# MCU.net
KiCad netlist of a schematic drawn in Altium Designer
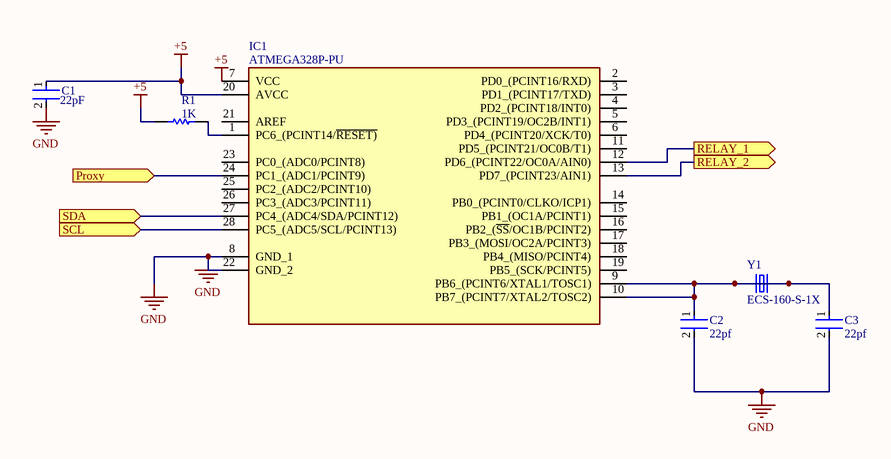
[diagram p0: MCU.SchDoc]

(export (version "E")
  (design (tool "Eeschema 10.0.6"))
  (components
    (comp (ref "C1")
      (value "22pF")
      (footprint "FP-VY2472M49Y5UG63V7-MFG")
      (description "Capacitor Ceramic 4700pF ±20% Y5U BULK RADIAL")
      (fields (field (name "TOLERANCE") "20%") (field (name "Comment") "22pf"))
      (libsource (lib "Altium Content Vault") (part "02cd4be3c70576c341d710602a673aa"))
    )
    (comp (ref "C2")
      (value "22pf")
      (footprint "FP-VY2472M49Y5UG63V7-MFG")
      (description "Capacitor Ceramic 4700pF ±20% Y5U BULK RADIAL")
      (fields (field (name "TOLERANCE") "20%"))
      (libsource (lib "Altium Content Vault") (part "02cd4be3c70576c341d710602a673aa"))
    )
    (comp (ref "C3")
      (value "22pf")
      (footprint "FP-VY2472M49Y5UG63V7-MFG")
      (description "Capacitor Ceramic 4700pF ±20% Y5U BULK RADIAL")
      (fields (field (name "TOLERANCE") "20%"))
      (libsource (lib "Altium Content Vault") (part "02cd4be3c70576c341d710602a673aa"))
    )
    (comp (ref "IC1")
      (value "ATMEGA328P-PU")
      (footprint "SamacSys:DIP794W53P254L3467H457Q28N")
      (description "Integrated Circuit")
      (fields (field (name "MOUSER PART NUMBER") "556-ATMEGA328P-PU"))
      (libsource (lib "*") (part "ATMEGA328P-PU"))
    )
    (comp (ref "R1")
      (value "1K")
      (footprint "RESA60-630X240")
      (description "Axial Resistor, 10 KOhm, +/- 1%, 0.25 W, -55 to 155 degC, 2-Pin THD, RoHS, Bulk")
      (fields (field (name "TOLERANCE") "1%") (field (name "MANUFACTURER") "Yageo"))
      (libsource (lib "Altium Content Vault") (part "RES-2"))
    )
    (comp (ref "Y1")
      (value "ECS-160-S-1X")
      (footprint "XTAL_ECS-160-S-1X")
      (description "16MHz Â±30ppm Crystal Series 20 Ohms HC-49/U")
      (fields (field (name "MF") "ECS Inc."))
      (libsource (lib "ECS-160-S-1X") (part "ECS-160-S-1X"))
    )
  )
  (nets
    (net (code "1") (name "+5") (class "Default")
      (node (ref "C1") (pin "1") (pinfunction "1_1") (pintype "passive"))
      (node (ref "IC1") (pin "20") (pinfunction "AVCC_20") (pintype "passive"))
      (node (ref "IC1") (pin "7") (pinfunction "VCC_7") (pintype "passive"))
      (node (ref "R1") (pin "1") (pinfunction "1_1") (pintype "passive"))
    )
    (net (code "2") (name "/Proxy") (class "Default")
      (node (ref "IC1") (pin "24") (pinfunction "PC1_(ADC1/PCINT9)_24") (pintype "passive"))
    )
    (net (code "3") (name "/RELAY_1") (class "Default")
      (node (ref "IC1") (pin "12") (pinfunction "PD6_(PCINT22/OC0A/AIN0)_12") (pintype "passive"))
    )
    (net (code "4") (name "/RELAY_2") (class "Default")
      (node (ref "IC1") (pin "13") (pinfunction "PD7_(PCINT23/AIN1)_13") (pintype "passive"))
    )
    (net (code "5") (name "/SCL") (class "Default")
      (node (ref "IC1") (pin "28") (pinfunction "PC5_(ADC5/SCL/PCINT13)_28") (pintype "passive"))
    )
    (net (code "6") (name "/SDA") (class "Default")
      (node (ref "IC1") (pin "27") (pinfunction "PC4_(ADC4/SDA/PCINT12)_27") (pintype "passive"))
    )
    (net (code "7") (name "GND") (class "Default")
      (node (ref "C1") (pin "2") (pinfunction "2_2") (pintype "passive"))
      (node (ref "C2") (pin "2") (pinfunction "2_2") (pintype "passive"))
      (node (ref "C3") (pin "2") (pinfunction "2_2") (pintype "passive"))
      (node (ref "IC1") (pin "22") (pinfunction "GND_2_22") (pintype "passive"))
      (node (ref "IC1") (pin "8") (pinfunction "GND_1_8") (pintype "passive"))
    )
    (net (code "8") (name "Net-(IC1-PB6_(PCINT6{slash}XTAL1{slash}TOSC1))") (class "Default")
      (node (ref "C2") (pin "1") (pinfunction "1_1") (pintype "passive"))
      (node (ref "C3") (pin "1") (pinfunction "1_1") (pintype "passive"))
      (node (ref "IC1") (pin "10") (pinfunction "PB7_(PCINT7/XTAL2/TOSC2)_10") (pintype "passive"))
      (node (ref "IC1") (pin "9") (pinfunction "PB6_(PCINT6/XTAL1/TOSC1)_9") (pintype "passive"))
      (node (ref "Y1") (pin "1") (pinfunction "1_1") (pintype "passive"))
      (node (ref "Y1") (pin "2") (pinfunction "2_2") (pintype "passive"))
    )
    (net (code "9") (name "Net-(IC1-PC6_(PCINT14{slash}~{RESET)})") (class "Default")
      (node (ref "IC1") (pin "1") (pinfunction "PC6_(PCINT14/~{RESET)}_1") (pintype "passive"))
      (node (ref "R1") (pin "2") (pinfunction "2_2") (pintype "passive"))
    )
    (net (code "10") (name "unconnected-(IC1-AREF-Pad21)") (class "Default")
      (node (ref "IC1") (pin "21") (pinfunction "AREF_21") (pintype "passive"))
    )
    (net (code "11") (name "unconnected-(IC1-PB0_(PCINT0{slash}CLKO{slash}ICP1)-Pad14)") (class "Default")
      (node (ref "IC1") (pin "14") (pinfunction "PB0_(PCINT0/CLKO/ICP1)_14") (pintype "passive"))
    )
    (net (code "12") (name "unconnected-(IC1-PB1_(OC1A{slash}PCINT1)-Pad15)") (class "Default")
      (node (ref "IC1") (pin "15") (pinfunction "PB1_(OC1A/PCINT1)_15") (pintype "passive"))
    )
    (net (code "13") (name "unconnected-(IC1-PB2_(~{SS}{slash}OC1B{slash}PCINT2)-Pad16)") (class "Default")
      (node (ref "IC1") (pin "16") (pinfunction "PB2_(~{SS}/OC1B/PCINT2)_16") (pintype "passive"))
    )
    (net (code "14") (name "unconnected-(IC1-PB3_(MOSI{slash}OC2A{slash}PCINT3)-Pad17)") (class "Default")
      (node (ref "IC1") (pin "17") (pinfunction "PB3_(MOSI/OC2A/PCINT3)_17") (pintype "passive"))
    )
    (net (code "15") (name "unconnected-(IC1-PB4_(MISO{slash}PCINT4)-Pad18)") (class "Default")
      (node (ref "IC1") (pin "18") (pinfunction "PB4_(MISO/PCINT4)_18") (pintype "passive"))
    )
    (net (code "16") (name "unconnected-(IC1-PB5_(SCK{slash}PCINT5)-Pad19)") (class "Default")
      (node (ref "IC1") (pin "19") (pinfunction "PB5_(SCK/PCINT5)_19") (pintype "passive"))
    )
    (net (code "17") (name "unconnected-(IC1-PC0_(ADC0{slash}PCINT8)-Pad23)") (class "Default")
      (node (ref "IC1") (pin "23") (pinfunction "PC0_(ADC0/PCINT8)_23") (pintype "passive"))
    )
    (net (code "18") (name "unconnected-(IC1-PC2_(ADC2{slash}PCINT10)-Pad25)") (class "Default")
      (node (ref "IC1") (pin "25") (pinfunction "PC2_(ADC2/PCINT10)_25") (pintype "passive"))
    )
    (net (code "19") (name "unconnected-(IC1-PC3_(ADC3{slash}PCINT11)-Pad26)") (class "Default")
      (node (ref "IC1") (pin "26") (pinfunction "PC3_(ADC3/PCINT11)_26") (pintype "passive"))
    )
    (net (code "20") (name "unconnected-(IC1-PD0_(PCINT16{slash}RXD)-Pad2)") (class "Default")
      (node (ref "IC1") (pin "2") (pinfunction "PD0_(PCINT16/RXD)_2") (pintype "passive"))
    )
    (net (code "21") (name "unconnected-(IC1-PD1_(PCINT17{slash}TXD)-Pad3)") (class "Default")
      (node (ref "IC1") (pin "3") (pinfunction "PD1_(PCINT17/TXD)_3") (pintype "passive"))
    )
    (net (code "22") (name "unconnected-(IC1-PD2_(PCINT18{slash}INT0)-Pad4)") (class "Default")
      (node (ref "IC1") (pin "4") (pinfunction "PD2_(PCINT18/INT0)_4") (pintype "passive"))
    )
    (net (code "23") (name "unconnected-(IC1-PD3_(PCINT19{slash}OC2B{slash}INT1)-Pad5)") (class "Default")
      (node (ref "IC1") (pin "5") (pinfunction "PD3_(PCINT19/OC2B/INT1)_5") (pintype "passive"))
    )
    (net (code "24") (name "unconnected-(IC1-PD4_(PCINT20{slash}XCK{slash}T0)-Pad6)") (class "Default")
      (node (ref "IC1") (pin "6") (pinfunction "PD4_(PCINT20/XCK/T0)_6") (pintype "passive"))
    )
    (net (code "25") (name "unconnected-(IC1-PD5_(PCINT21{slash}OC0B{slash}T1)-Pad11)") (class "Default")
      (node (ref "IC1") (pin "11") (pinfunction "PD5_(PCINT21/OC0B/T1)_11") (pintype "passive"))
    )
  )
)
